# MainBoard.net
KiCad netlist of a schematic drawn in EAGLE
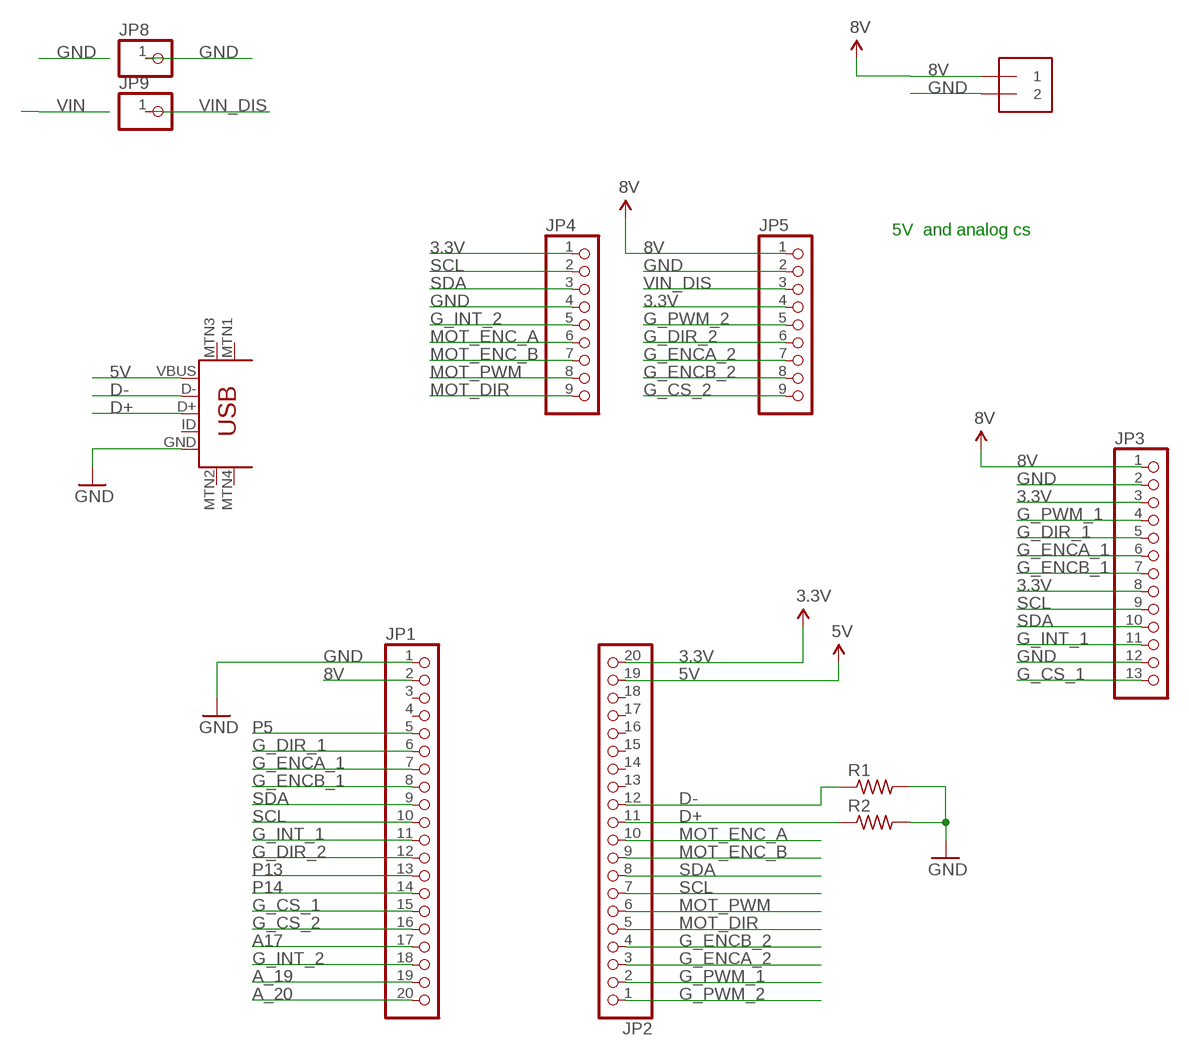
[diagram p0: schematic, sheet 1]

(export (version "E")
  (design (tool "Eeschema 10.0.6"))
  (components
    (comp (ref "J1")
      (value "1X2-3.5MM")
      (footprint "eagle-import:1X2-3.5MM")
      (libsource (lib "eagle-import") (part "1X2-3.5MM"))
    )
    (comp (ref "JP1")
      (value "PINHD-1X20")
      (footprint "eagle-import:1X20")
      (libsource (lib "eagle-import") (part "PINHD-1X20"))
    )
    (comp (ref "JP2")
      (value "PINHD-1X20")
      (footprint "eagle-import:1X20")
      (libsource (lib "eagle-import") (part "PINHD-1X20"))
    )
    (comp (ref "JP3")
      (value "PINHD-1X13")
      (footprint "eagle-import:1X13")
      (libsource (lib "eagle-import") (part "PINHD-1X13"))
    )
    (comp (ref "JP4")
      (value "PINHD-1X9")
      (footprint "eagle-import:1X09-BIG")
      (libsource (lib "eagle-import") (part "PINHD-1X9"))
    )
    (comp (ref "JP5")
      (value "PINHD-1X9")
      (footprint "eagle-import:1X09-BIG")
      (libsource (lib "eagle-import") (part "PINHD-1X9"))
    )
    (comp (ref "JP8")
      (value "PINHD-1X1")
      (footprint "eagle-import:1X01")
      (libsource (lib "eagle-import") (part "PINHD-1X1"))
    )
    (comp (ref "JP9")
      (value "PINHD-1X1")
      (footprint "eagle-import:1X01")
      (libsource (lib "eagle-import") (part "PINHD-1X1"))
    )
    (comp (ref "R1")
      (value "RES-US1206")
      (footprint "eagle-import:R1206")
      (libsource (lib "eagle-import") (part "RES-US1206"))
    )
    (comp (ref "R2")
      (value "RES-US1206")
      (footprint "eagle-import:R1206")
      (libsource (lib "eagle-import") (part "RES-US1206"))
    )
    (comp (ref "U$1")
      (value "USB-MINIB-5PIN")
      (footprint "eagle-import:USB-MINIB")
      (libsource (lib "eagle-import") (part "USB-MINIB-5PIN"))
    )
  )
  (nets
    (net (code "1") (name "/A17") (class "Default")
      (node (ref "JP1") (pin "17") (pinfunction "17_17") (pintype "passive"))
    )
    (net (code "2") (name "/A_19") (class "Default")
      (node (ref "JP1") (pin "19") (pinfunction "19_19") (pintype "passive"))
    )
    (net (code "3") (name "/A_20") (class "Default")
      (node (ref "JP1") (pin "20") (pinfunction "20_20") (pintype "passive"))
    )
    (net (code "4") (name "/D+") (class "Default")
      (node (ref "JP2") (pin "11") (pinfunction "11_11") (pintype "passive"))
      (node (ref "R2") (pin "1") (pinfunction "1_1") (pintype "passive"))
      (node (ref "U$1") (pin "D+") (pinfunction "D+_D+") (pintype "bidirectional"))
    )
    (net (code "5") (name "/D-") (class "Default")
      (node (ref "JP2") (pin "12") (pinfunction "12_12") (pintype "passive"))
      (node (ref "R1") (pin "1") (pinfunction "1_1") (pintype "passive"))
      (node (ref "U$1") (pin "D-") (pinfunction "D-_D-") (pintype "bidirectional"))
    )
    (net (code "6") (name "/G_CS_1") (class "Default")
      (node (ref "JP1") (pin "15") (pinfunction "15_15") (pintype "passive"))
      (node (ref "JP3") (pin "13") (pinfunction "13_13") (pintype "passive"))
    )
    (net (code "7") (name "/G_CS_2") (class "Default")
      (node (ref "JP1") (pin "16") (pinfunction "16_16") (pintype "passive"))
      (node (ref "JP5") (pin "9") (pinfunction "9_9") (pintype "passive"))
    )
    (net (code "8") (name "/G_DIR_1") (class "Default")
      (node (ref "JP1") (pin "6") (pinfunction "6_6") (pintype "passive"))
      (node (ref "JP3") (pin "5") (pinfunction "5_5") (pintype "passive"))
    )
    (net (code "9") (name "/G_DIR_2") (class "Default")
      (node (ref "JP1") (pin "12") (pinfunction "12_12") (pintype "passive"))
      (node (ref "JP5") (pin "6") (pinfunction "6_6") (pintype "passive"))
    )
    (net (code "10") (name "/G_ENCA_1") (class "Default")
      (node (ref "JP1") (pin "7") (pinfunction "7_7") (pintype "passive"))
      (node (ref "JP3") (pin "6") (pinfunction "6_6") (pintype "passive"))
    )
    (net (code "11") (name "/G_ENCA_2") (class "Default")
      (node (ref "JP2") (pin "3") (pinfunction "3_3") (pintype "passive"))
      (node (ref "JP5") (pin "7") (pinfunction "7_7") (pintype "passive"))
    )
    (net (code "12") (name "/G_ENCB_1") (class "Default")
      (node (ref "JP1") (pin "8") (pinfunction "8_8") (pintype "passive"))
      (node (ref "JP3") (pin "7") (pinfunction "7_7") (pintype "passive"))
    )
    (net (code "13") (name "/G_ENCB_2") (class "Default")
      (node (ref "JP2") (pin "4") (pinfunction "4_4") (pintype "passive"))
      (node (ref "JP5") (pin "8") (pinfunction "8_8") (pintype "passive"))
    )
    (net (code "14") (name "/G_INT_1") (class "Default")
      (node (ref "JP1") (pin "11") (pinfunction "11_11") (pintype "passive"))
      (node (ref "JP3") (pin "11") (pinfunction "11_11") (pintype "passive"))
    )
    (net (code "15") (name "/G_INT_2") (class "Default")
      (node (ref "JP1") (pin "18") (pinfunction "18_18") (pintype "passive"))
      (node (ref "JP4") (pin "5") (pinfunction "5_5") (pintype "passive"))
    )
    (net (code "16") (name "/G_PWM_1") (class "Default")
      (node (ref "JP2") (pin "2") (pinfunction "2_2") (pintype "passive"))
      (node (ref "JP3") (pin "4") (pinfunction "4_4") (pintype "passive"))
    )
    (net (code "17") (name "/G_PWM_2") (class "Default")
      (node (ref "JP2") (pin "1") (pinfunction "1_1") (pintype "passive"))
      (node (ref "JP5") (pin "5") (pinfunction "5_5") (pintype "passive"))
    )
    (net (code "18") (name "/MOT_DIR") (class "Default")
      (node (ref "JP2") (pin "5") (pinfunction "5_5") (pintype "passive"))
      (node (ref "JP4") (pin "9") (pinfunction "9_9") (pintype "passive"))
    )
    (net (code "19") (name "/MOT_ENC_A") (class "Default")
      (node (ref "JP2") (pin "10") (pinfunction "10_10") (pintype "passive"))
      (node (ref "JP4") (pin "6") (pinfunction "6_6") (pintype "passive"))
    )
    (net (code "20") (name "/MOT_ENC_B") (class "Default")
      (node (ref "JP2") (pin "9") (pinfunction "9_9") (pintype "passive"))
      (node (ref "JP4") (pin "7") (pinfunction "7_7") (pintype "passive"))
    )
    (net (code "21") (name "/MOT_PWM") (class "Default")
      (node (ref "JP2") (pin "6") (pinfunction "6_6") (pintype "passive"))
      (node (ref "JP4") (pin "8") (pinfunction "8_8") (pintype "passive"))
    )
    (net (code "22") (name "/P5") (class "Default")
      (node (ref "JP1") (pin "5") (pinfunction "5_5") (pintype "passive"))
    )
    (net (code "23") (name "/P13") (class "Default")
      (node (ref "JP1") (pin "13") (pinfunction "13_13") (pintype "passive"))
    )
    (net (code "24") (name "/P14") (class "Default")
      (node (ref "JP1") (pin "14") (pinfunction "14_14") (pintype "passive"))
    )
    (net (code "25") (name "/SCL") (class "Default")
      (node (ref "JP1") (pin "10") (pinfunction "10_10") (pintype "passive"))
      (node (ref "JP2") (pin "7") (pinfunction "7_7") (pintype "passive"))
      (node (ref "JP3") (pin "9") (pinfunction "9_9") (pintype "passive"))
      (node (ref "JP4") (pin "2") (pinfunction "2_2") (pintype "passive"))
    )
    (net (code "26") (name "/SDA") (class "Default")
      (node (ref "JP1") (pin "9") (pinfunction "9_9") (pintype "passive"))
      (node (ref "JP2") (pin "8") (pinfunction "8_8") (pintype "passive"))
      (node (ref "JP3") (pin "10") (pinfunction "10_10") (pintype "passive"))
      (node (ref "JP4") (pin "3") (pinfunction "3_3") (pintype "passive"))
    )
    (net (code "28") (name "/VIN_DIS") (class "Default")
      (node (ref "JP5") (pin "3") (pinfunction "3_3") (pintype "passive"))
      (node (ref "JP9") (pin "1") (pinfunction "1_1") (pintype "passive"))
    )
    (net (code "29") (name "3.3V") (class "Default")
      (node (ref "JP2") (pin "20") (pinfunction "20_20") (pintype "passive"))
      (node (ref "JP3") (pin "3") (pinfunction "3_3") (pintype "passive"))
      (node (ref "JP3") (pin "8") (pinfunction "8_8") (pintype "passive"))
      (node (ref "JP4") (pin "1") (pinfunction "1_1") (pintype "passive"))
      (node (ref "JP5") (pin "4") (pinfunction "4_4") (pintype "passive"))
    )
    (net (code "30") (name "5V") (class "Default")
      (node (ref "JP2") (pin "19") (pinfunction "19_19") (pintype "passive"))
      (node (ref "U$1") (pin "VBUS") (pinfunction "VBUS_VBUS") (pintype "bidirectional"))
    )
    (net (code "31") (name "8V") (class "Default")
      (node (ref "J1") (pin "1") (pinfunction "1_1") (pintype "passive"))
      (node (ref "JP1") (pin "2") (pinfunction "2_2") (pintype "passive"))
      (node (ref "JP3") (pin "1") (pinfunction "1_1") (pintype "passive"))
      (node (ref "JP5") (pin "1") (pinfunction "1_1") (pintype "passive"))
    )
    (net (code "32") (name "GND") (class "Default")
      (node (ref "J1") (pin "2") (pinfunction "2_2") (pintype "passive"))
      (node (ref "JP1") (pin "1") (pinfunction "1_1") (pintype "passive"))
      (node (ref "JP3") (pin "12") (pinfunction "12_12") (pintype "passive"))
      (node (ref "JP3") (pin "2") (pinfunction "2_2") (pintype "passive"))
      (node (ref "JP4") (pin "4") (pinfunction "4_4") (pintype "passive"))
      (node (ref "JP5") (pin "2") (pinfunction "2_2") (pintype "passive"))
      (node (ref "JP8") (pin "1") (pinfunction "1_1") (pintype "passive"))
      (node (ref "R1") (pin "2") (pinfunction "2_2") (pintype "passive"))
      (node (ref "R2") (pin "2") (pinfunction "2_2") (pintype "passive"))
      (node (ref "U$1") (pin "GND") (pinfunction "GND_GND") (pintype "bidirectional"))
    )
    (net (code "33") (name "unconnected-(JP1-Pad3)") (class "Default")
      (node (ref "JP1") (pin "3") (pinfunction "3_3") (pintype "passive"))
    )
    (net (code "34") (name "unconnected-(JP1-Pad4)") (class "Default")
      (node (ref "JP1") (pin "4") (pinfunction "4_4") (pintype "passive"))
    )
    (net (code "35") (name "unconnected-(JP2-Pad13)") (class "Default")
      (node (ref "JP2") (pin "13") (pinfunction "13_13") (pintype "passive"))
    )
    (net (code "36") (name "unconnected-(JP2-Pad14)") (class "Default")
      (node (ref "JP2") (pin "14") (pinfunction "14_14") (pintype "passive"))
    )
    (net (code "37") (name "unconnected-(JP2-Pad15)") (class "Default")
      (node (ref "JP2") (pin "15") (pinfunction "15_15") (pintype "passive"))
    )
    (net (code "38") (name "unconnected-(JP2-Pad16)") (class "Default")
      (node (ref "JP2") (pin "16") (pinfunction "16_16") (pintype "passive"))
    )
    (net (code "39") (name "unconnected-(JP2-Pad17)") (class "Default")
      (node (ref "JP2") (pin "17") (pinfunction "17_17") (pintype "passive"))
    )
    (net (code "40") (name "unconnected-(JP2-Pad18)") (class "Default")
      (node (ref "JP2") (pin "18") (pinfunction "18_18") (pintype "passive"))
    )
    (net (code "41") (name "unconnected-(U$1-MTN1-PadMTN3)") (class "Default")
      (node (ref "U$1") (pin "MTN3") (pinfunction "MTN1_MTN3") (pintype "bidirectional"))
    )
    (net (code "42") (name "unconnected-(U$1-MTN2-PadMTN1)") (class "Default")
      (node (ref "U$1") (pin "MTN1") (pinfunction "MTN2_MTN1") (pintype "bidirectional"))
    )
    (net (code "43") (name "unconnected-(U$1-MTN3-PadMTN2)") (class "Default")
      (node (ref "U$1") (pin "MTN2") (pinfunction "MTN3_MTN2") (pintype "bidirectional"))
    )
    (net (code "44") (name "unconnected-(U$1-PadID)") (class "Default")
      (node (ref "U$1") (pin "ID") (pinfunction "ID_ID") (pintype "bidirectional"))
    )
    (net (code "45") (name "unconnected-(U$1-PadMTN4)") (class "Default")
      (node (ref "U$1") (pin "MTN4") (pinfunction "MTN4_MTN4") (pintype "bidirectional"))
    )
  )
)
